# mini_button.net
KiCad netlist of a schematic drawn in EAGLE
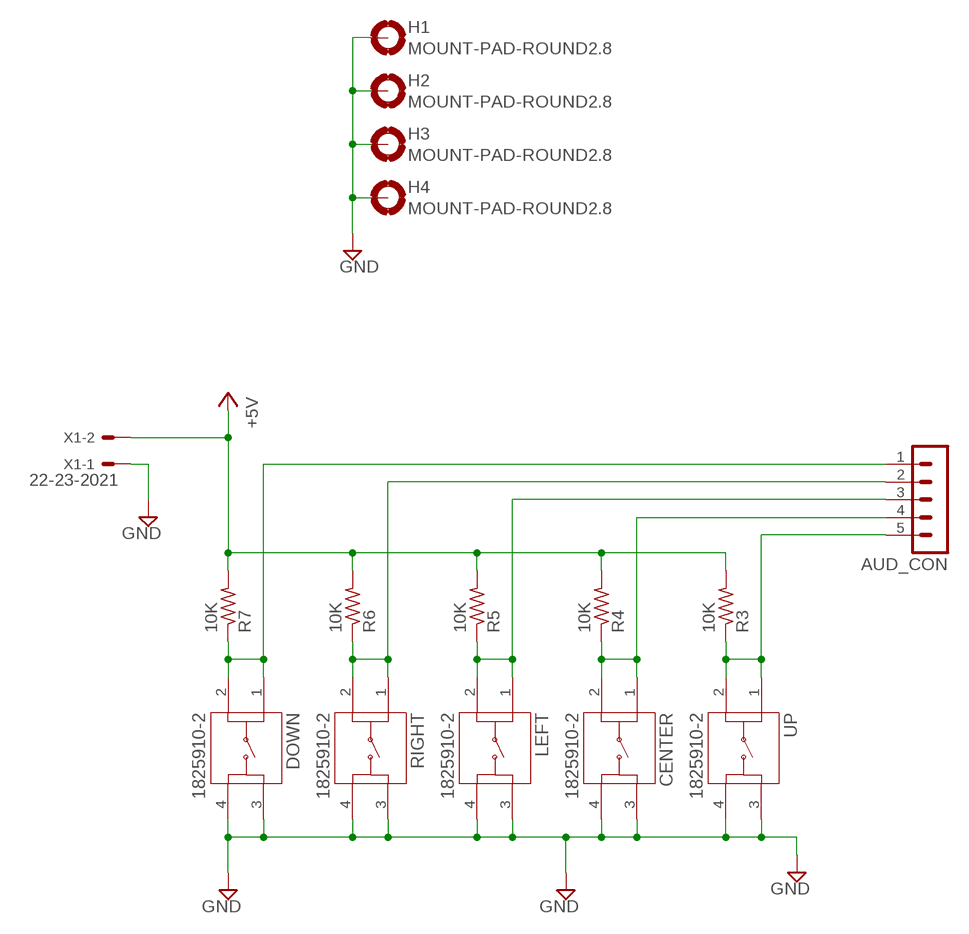
[diagram p0: schematic, sheet 1]

(export (version "E")
  (design (tool "Eeschema 10.0.6"))
  (components
    (comp (ref "AUD_CON")
      (value "MA05-1")
      (footprint "eagle-import:MA05-1")
      (libsource (lib "eagle-import") (part "MA05-1"))
    )
    (comp (ref "CENTER")
      (value "1825910-2")
      (footprint "eagle-import:TE_1825910-2")
      (fields (field (name "MANUFACTURER") "TE CONNECTIVITY"))
      (libsource (lib "eagle-import") (part "1825910-2"))
    )
    (comp (ref "DOWN")
      (value "1825910-2")
      (footprint "eagle-import:TE_1825910-2")
      (fields (field (name "MANUFACTURER") "TE CONNECTIVITY"))
      (libsource (lib "eagle-import") (part "1825910-2"))
    )
    (comp (ref "H1")
      (value "MOUNT-PAD-ROUND2.8")
      (footprint "eagle-import:2,8-PAD")
      (libsource (lib "eagle-import") (part "MOUNT-PAD-ROUND2.8"))
    )
    (comp (ref "H2")
      (value "MOUNT-PAD-ROUND2.8")
      (footprint "eagle-import:2,8-PAD")
      (libsource (lib "eagle-import") (part "MOUNT-PAD-ROUND2.8"))
    )
    (comp (ref "H3")
      (value "MOUNT-PAD-ROUND2.8")
      (footprint "eagle-import:2,8-PAD")
      (libsource (lib "eagle-import") (part "MOUNT-PAD-ROUND2.8"))
    )
    (comp (ref "H4")
      (value "MOUNT-PAD-ROUND2.8")
      (footprint "eagle-import:2,8-PAD")
      (libsource (lib "eagle-import") (part "MOUNT-PAD-ROUND2.8"))
    )
    (comp (ref "LEFT")
      (value "1825910-2")
      (footprint "eagle-import:TE_1825910-2")
      (fields (field (name "MANUFACTURER") "TE CONNECTIVITY"))
      (libsource (lib "eagle-import") (part "1825910-2"))
    )
    (comp (ref "R3")
      (value "10K")
      (footprint "eagle-import:0204_7")
      (libsource (lib "eagle-import") (part "R-US_0204/7"))
    )
    (comp (ref "R4")
      (value "10K")
      (footprint "eagle-import:0204_7")
      (libsource (lib "eagle-import") (part "R-US_0204/7"))
    )
    (comp (ref "R5")
      (value "10K")
      (footprint "eagle-import:0204_7")
      (libsource (lib "eagle-import") (part "R-US_0204/7"))
    )
    (comp (ref "R6")
      (value "10K")
      (footprint "eagle-import:0204_7")
      (libsource (lib "eagle-import") (part "R-US_0204/7"))
    )
    (comp (ref "R7")
      (value "10K")
      (footprint "eagle-import:0204_7")
      (libsource (lib "eagle-import") (part "R-US_0204/7"))
    )
    (comp (ref "RIGHT")
      (value "1825910-2")
      (footprint "eagle-import:TE_1825910-2")
      (fields (field (name "MANUFACTURER") "TE CONNECTIVITY"))
      (libsource (lib "eagle-import") (part "1825910-2"))
    )
    (comp (ref "UP")
      (value "1825910-2")
      (footprint "eagle-import:TE_1825910-2")
      (fields (field (name "MANUFACTURER") "TE CONNECTIVITY"))
      (libsource (lib "eagle-import") (part "1825910-2"))
    )
    (comp (ref "X1")
      (value "22-23-2021")
      (footprint "eagle-import:22-23-2021")
      (fields (field (name "MF") "MOLEX"))
      (libsource (lib "eagle-import") (part "22-23-2021"))
    )
  )
  (nets
    (net (code "1") (name "+5V") (class "Default")
      (node (ref "R3") (pin "2") (pinfunction "2_2") (pintype "passive"))
      (node (ref "R4") (pin "2") (pinfunction "2_2") (pintype "passive"))
      (node (ref "R5") (pin "2") (pinfunction "2_2") (pintype "passive"))
      (node (ref "R6") (pin "2") (pinfunction "2_2") (pintype "passive"))
      (node (ref "R7") (pin "2") (pinfunction "2_2") (pintype "passive"))
      (node (ref "X1") (pin "2") (pinfunction "S_2") (pintype "passive"))
    )
    (net (code "2") (name "GND") (class "Default")
      (node (ref "CENTER") (pin "3") (pinfunction "3_3") (pintype "passive"))
      (node (ref "CENTER") (pin "4") (pinfunction "4_4") (pintype "passive"))
      (node (ref "DOWN") (pin "3") (pinfunction "3_3") (pintype "passive"))
      (node (ref "DOWN") (pin "4") (pinfunction "4_4") (pintype "passive"))
      (node (ref "H1") (pin "B2,8") (pinfunction "MOUNT_B2,8") (pintype "passive"))
      (node (ref "H2") (pin "B2,8") (pinfunction "MOUNT_B2,8") (pintype "passive"))
      (node (ref "H3") (pin "B2,8") (pinfunction "MOUNT_B2,8") (pintype "passive"))
      (node (ref "H4") (pin "B2,8") (pinfunction "MOUNT_B2,8") (pintype "passive"))
      (node (ref "LEFT") (pin "3") (pinfunction "3_3") (pintype "passive"))
      (node (ref "LEFT") (pin "4") (pinfunction "4_4") (pintype "passive"))
      (node (ref "RIGHT") (pin "3") (pinfunction "3_3") (pintype "passive"))
      (node (ref "RIGHT") (pin "4") (pinfunction "4_4") (pintype "passive"))
      (node (ref "UP") (pin "3") (pinfunction "3_3") (pintype "passive"))
      (node (ref "UP") (pin "4") (pinfunction "4_4") (pintype "passive"))
      (node (ref "X1") (pin "1") (pinfunction "S_1") (pintype "passive"))
    )
    (net (code "3") (name "Net-(AUD_CON-Pad1)") (class "Default")
      (node (ref "AUD_CON") (pin "1") (pinfunction "1_1") (pintype "passive"))
      (node (ref "DOWN") (pin "1") (pinfunction "1_1") (pintype "passive"))
      (node (ref "DOWN") (pin "2") (pinfunction "2_2") (pintype "passive"))
      (node (ref "R7") (pin "1") (pinfunction "1_1") (pintype "passive"))
    )
    (net (code "4") (name "Net-(AUD_CON-Pad2)") (class "Default")
      (node (ref "AUD_CON") (pin "2") (pinfunction "2_2") (pintype "passive"))
      (node (ref "R6") (pin "1") (pinfunction "1_1") (pintype "passive"))
      (node (ref "RIGHT") (pin "1") (pinfunction "1_1") (pintype "passive"))
      (node (ref "RIGHT") (pin "2") (pinfunction "2_2") (pintype "passive"))
    )
    (net (code "5") (name "Net-(AUD_CON-Pad3)") (class "Default")
      (node (ref "AUD_CON") (pin "3") (pinfunction "3_3") (pintype "passive"))
      (node (ref "LEFT") (pin "1") (pinfunction "1_1") (pintype "passive"))
      (node (ref "LEFT") (pin "2") (pinfunction "2_2") (pintype "passive"))
      (node (ref "R5") (pin "1") (pinfunction "1_1") (pintype "passive"))
    )
    (net (code "6") (name "Net-(AUD_CON-Pad4)") (class "Default")
      (node (ref "AUD_CON") (pin "4") (pinfunction "4_4") (pintype "passive"))
      (node (ref "CENTER") (pin "1") (pinfunction "1_1") (pintype "passive"))
      (node (ref "CENTER") (pin "2") (pinfunction "2_2") (pintype "passive"))
      (node (ref "R4") (pin "1") (pinfunction "1_1") (pintype "passive"))
    )
    (net (code "7") (name "Net-(AUD_CON-Pad5)") (class "Default")
      (node (ref "AUD_CON") (pin "5") (pinfunction "5_5") (pintype "passive"))
      (node (ref "R3") (pin "1") (pinfunction "1_1") (pintype "passive"))
      (node (ref "UP") (pin "1") (pinfunction "1_1") (pintype "passive"))
      (node (ref "UP") (pin "2") (pinfunction "2_2") (pintype "passive"))
    )
  )
)
